# ST_LINK_V2-1.net
KiCad netlist of a schematic drawn in Altium Designer
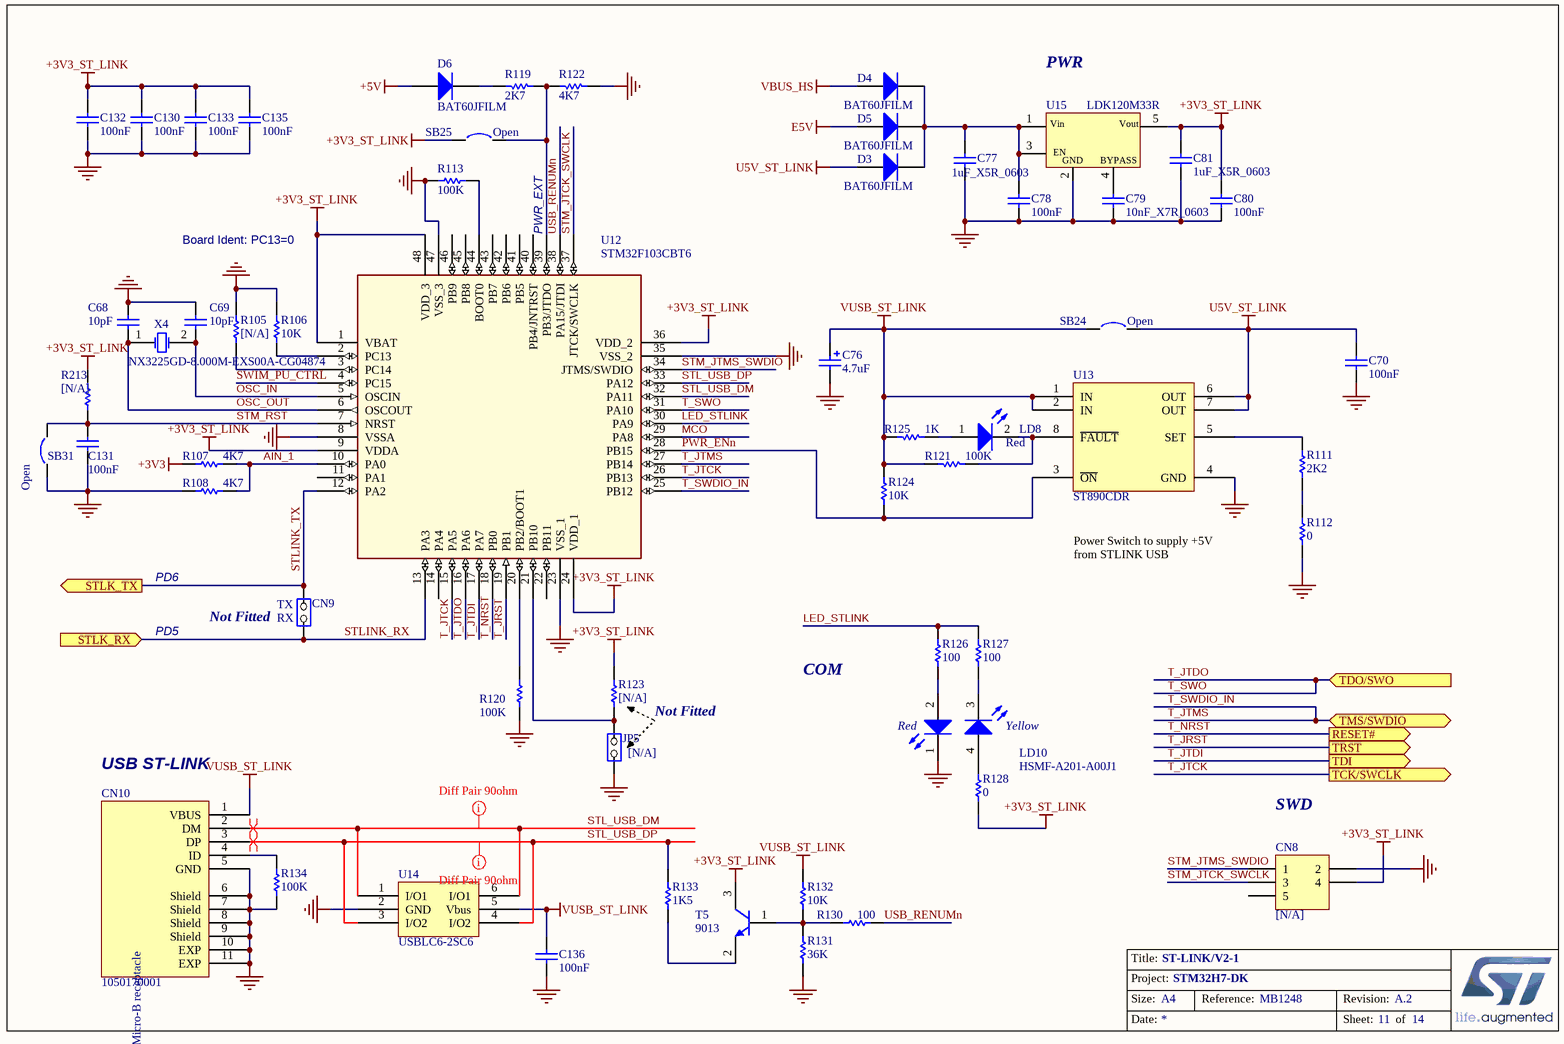
[diagram p0: ST_LINK_V2-1.SCHDOC]

(export (version "E")
  (design (tool "Eeschema 10.0.6"))
  (components
    (comp (ref "C68")
      (value "10pF")
      (footprint "0603C")
      (description "Capacitor 0402 / 0603 / 0805")
      (libsource (lib "MCD_TOOLS") (part "Capacitor_ST"))
    )
    (comp (ref "C69")
      (value "10pF")
      (footprint "0603C")
      (description "Capacitor 0402 / 0603 / 0805")
      (libsource (lib "MCD_TOOLS") (part "Capacitor_ST"))
    )
    (comp (ref "C70")
      (value "100nF")
      (footprint "0603C")
      (description "Capacitor 0402 / 0603 / 0805")
      (libsource (lib "MCD_TOOLS") (part "Capacitor_ST"))
    )
    (comp (ref "C76")
      (value "4.7uF")
      (footprint "TAN-A")
      (description "Polarized Capacitor (Radial)")
      (fields (field (name "PUBLISHER") "Altium Limited"))
      (libsource (lib "*") (part "Cap Pol1"))
    )
    (comp (ref "C77")
      (value "1uF_X5R_0603")
      (footprint "0603C")
      (description "0603  X5R 1µF")
      (fields (field (name "TOLERANCE") "10%"))
      (libsource (lib "MB963_1") (part "CAP SMD 0603  X5R 1µF 25V 10%"))
    )
    (comp (ref "C78")
      (value "100nF")
      (footprint "0603C")
      (description "Capacitor 0402 / 0603 / 0805")
      (libsource (lib "MCD_TOOLS") (part "Capacitor_ST"))
    )
    (comp (ref "C79")
      (value "10nF_X7R_0603")
      (footprint "0603C")
      (description "0603  X7R 10NF")
      (fields (field (name "TOLERANCE") "10%"))
      (libsource (lib "MB963_1") (part "CAP SMD 0603  X7R 10000PF 50V 10%"))
    )
    (comp (ref "C80")
      (value "100nF")
      (footprint "0603C")
      (description "Capacitor 0402 / 0603 / 0805")
      (libsource (lib "MCD_TOOLS") (part "Capacitor_ST"))
    )
    (comp (ref "C81")
      (value "1uF_X5R_0603")
      (footprint "0603C")
      (description "0603  X5R 1µF")
      (fields (field (name "TOLERANCE") "10%"))
      (libsource (lib "MB963_1") (part "CAP SMD 0603  X5R 1µF 25V 10%"))
    )
    (comp (ref "C130")
      (value "100nF")
      (footprint "0603C")
      (description "Capacitor 0402 / 0603 / 0805")
      (libsource (lib "MCD_TOOLS") (part "Capacitor_ST"))
    )
    (comp (ref "C131")
      (value "100nF")
      (footprint "0603C")
      (description "Capacitor 0402 / 0603 / 0805")
      (libsource (lib "MCD_TOOLS") (part "Capacitor_ST"))
    )
    (comp (ref "C132")
      (value "100nF")
      (footprint "0603C")
      (description "Capacitor 0402 / 0603 / 0805")
      (libsource (lib "MCD_TOOLS") (part "Capacitor_ST"))
    )
    (comp (ref "C133")
      (value "100nF")
      (footprint "0603C")
      (description "Capacitor 0402 / 0603 / 0805")
      (libsource (lib "MCD_TOOLS") (part "Capacitor_ST"))
    )
    (comp (ref "C135")
      (value "100nF")
      (footprint "0603C")
      (description "Capacitor 0402 / 0603 / 0805")
      (libsource (lib "MCD_TOOLS") (part "Capacitor_ST"))
    )
    (comp (ref "C136")
      (value "100nF")
      (footprint "0603C")
      (description "Capacitor 0402 / 0603 / 0805")
      (libsource (lib "MCD_TOOLS") (part "Capacitor_ST"))
    )
    (comp (ref "CN8")
      (value "[N/A]")
      (footprint "HDR_2X3-1_2R54-6")
      (description "Header, 3-Pin, Dual row")
      (fields (field (name "PUBLISHER") "Altium Limited"))
      (libsource (lib "Miscellaneous Connectors") (part "Header 3X2"))
    )
    (comp (ref "CN9") (value "[N/A]") (footprint "SIP2") (libsource (lib "MCD_TOOLS") (part "JP2")))
    (comp (ref "CN10")
      (value "1050170001")
      (footprint "MICRO_USB_B_105017")
      (libsource (lib "Smartphone_accessory") (part "1050170001"))
    )
    (comp (ref "D3")
      (value "BAT60JFILM")
      (footprint "SOD-323")
      (libsource (lib "MCD_TOOLS") (part "BAT60JFILM"))
    )
    (comp (ref "D4")
      (value "BAT60JFILM")
      (footprint "SOD-323")
      (libsource (lib "MCD_TOOLS") (part "BAT60JFILM"))
    )
    (comp (ref "D5")
      (value "BAT60JFILM")
      (footprint "SOD-323")
      (libsource (lib "MCD_TOOLS") (part "BAT60JFILM"))
    )
    (comp (ref "D6")
      (value "BAT60JFILM")
      (footprint "SOD-323")
      (description "Default Diode")
      (fields (field (name "PUBLISHER") "Altium Limited"))
      (libsource (lib "MB1144_1") (part "Diode"))
    )
    (comp (ref "JP5") (value "[N/A]") (footprint "SIP2") (libsource (lib "*") (part "JP2")))
    (comp (ref "LD8")
      (value "Red")
      (footprint "0603D")
      (description "Typical RED, GREEN, YELLOW, AMBER GaAs LED")
      (fields (field (name "PUBLISHER") "Altium Limited"))
      (libsource (lib "Miscellaneous Devices") (part "LED2"))
    )
    (comp (ref "LD10")
      (value "HSMF-A201-A00J1")
      (footprint "LED2_3528")
      (libsource (lib "MB819") (part "HSMF-A201-A00J1"))
    )
    (comp (ref "R105")
      (value "[N/A]")
      (footprint "0603R")
      (description "Resistor 0402 or 0603 or 0805")
      (libsource (lib "") (part "Res1_1"))
    )
    (comp (ref "R106")
      (value "10K")
      (footprint "0603R")
      (description "Resistor 0402 or 0603 or 0805")
      (libsource (lib "") (part "Res1_1"))
    )
    (comp (ref "R107")
      (value "4K7")
      (footprint "0603R")
      (description "Resistor 0402 or 0603 or 0805")
      (libsource (lib "") (part "Res1_1"))
    )
    (comp (ref "R108")
      (value "4K7")
      (footprint "0603R")
      (description "Resistor 0402 or 0603 or 0805")
      (libsource (lib "") (part "Res1_1"))
    )
    (comp (ref "R111")
      (value "2K2")
      (footprint "0402R")
      (description "Resistor 0402 or 0603 or 0805")
      (libsource (lib "MCD_TOOLS") (part "Resistor_ST"))
    )
    (comp (ref "R112")
      (value "0")
      (footprint "0603R")
      (description "Resistor")
      (fields (field (name "PUBLISHER") "Altium Limited"))
      (libsource (lib "") (part "Res1_2"))
    )
    (comp (ref "R113")
      (value "100K")
      (footprint "0603R")
      (description "Resistor 0402 or 0603 or 0805")
      (libsource (lib "") (part "Res1_1"))
    )
    (comp (ref "R119")
      (value "2K7")
      (footprint "0603R")
      (description "Resistor")
      (fields (field (name "PUBLISHER") "Altium Limited"))
      (libsource (lib "Miscellaneous Devices") (part "Res1"))
    )
    (comp (ref "R120")
      (value "100K")
      (footprint "0603R")
      (description "Resistor 0402 or 0603 or 0805")
      (libsource (lib "") (part "Res1_1"))
    )
    (comp (ref "R121")
      (value "100K")
      (footprint "0603R")
      (description "Resistor")
      (fields (field (name "PUBLISHER") "Altium Limited"))
      (libsource (lib "*") (part "Res1"))
    )
    (comp (ref "R122")
      (value "4K7")
      (footprint "0603R")
      (description "Resistor")
      (fields (field (name "PUBLISHER") "Altium Limited"))
      (libsource (lib "Miscellaneous Devices") (part "Res1"))
    )
    (comp (ref "R123")
      (value "[N/A]")
      (footprint "0603R")
      (description "Resistor")
      (fields (field (name "PUBLISHER") "Altium Limited"))
      (libsource (lib "") (part "Res1_2"))
    )
    (comp (ref "R124")
      (value "10K")
      (footprint "0402R")
      (description "Resistor 0402 or 0603 or 0805")
      (libsource (lib "MCD_TOOLS") (part "Resistor_ST"))
    )
    (comp (ref "R125")
      (value "1K")
      (footprint "0603R")
      (description "Resistor")
      (fields (field (name "PUBLISHER") "Altium Limited"))
      (libsource (lib "*") (part "Res1"))
    )
    (comp (ref "R126")
      (value "100")
      (footprint "0603R")
      (description "Resistor")
      (fields (field (name "PUBLISHER") "Altium Limited"))
      (libsource (lib "") (part "Res1_2"))
    )
    (comp (ref "R127")
      (value "100")
      (footprint "0603R")
      (description "Resistor")
      (fields (field (name "PUBLISHER") "Altium Limited"))
      (libsource (lib "") (part "Res1_2"))
    )
    (comp (ref "R128")
      (value "0")
      (footprint "0603R")
      (description "Resistor")
      (fields (field (name "PUBLISHER") "Altium Limited"))
      (libsource (lib "") (part "Res1_2"))
    )
    (comp (ref "R130")
      (value "100")
      (footprint "0603R")
      (description "Resistor 0402 or 0603 or 0805")
      (libsource (lib "") (part "Res1_1"))
    )
    (comp (ref "R131")
      (value "36K")
      (footprint "0603R")
      (description "Resistor")
      (fields (field (name "PUBLISHER") "Altium Limited"))
      (libsource (lib "") (part "Res1_2"))
    )
    (comp (ref "R132")
      (value "10K")
      (footprint "0603R")
      (description "Resistor")
      (fields (field (name "PUBLISHER") "Altium Limited"))
      (libsource (lib "") (part "Res1_2"))
    )
    (comp (ref "R133")
      (value "1K5")
      (footprint "0603R")
      (description "Resistor 0402 or 0603 or 0805")
      (libsource (lib "") (part "Res1_1"))
    )
    (comp (ref "R134")
      (value "100K")
      (footprint "0603R")
      (description "Resistor 0402 or 0603 or 0805")
      (libsource (lib "") (part "Res1_1"))
    )
    (comp (ref "R213")
      (value "[N/A]")
      (footprint "0603R")
      (description "Resistor 0402 or 0603 or 0805")
      (libsource (lib "") (part "Res1_1"))
    )
    (comp (ref "SB24")
      (value "Open")
      (footprint "SB_0603")
      (description "Circuit Breaker")
      (fields (field (name "PUBLISHER") "Altium Limited"))
      (libsource (lib "MB1165") (part "Circuit Breaker"))
    )
    (comp (ref "SB25")
      (value "Open")
      (footprint "SB_0603")
      (description "Circuit Breaker")
      (fields (field (name "PUBLISHER") "Altium Limited"))
      (libsource (lib "MB1165") (part "Circuit Breaker"))
    )
    (comp (ref "SB31")
      (value "Open")
      (footprint "SB_0603")
      (description "Circuit Breaker")
      (fields (field (name "PUBLISHER") "Altium Limited"))
      (libsource (lib "MB1165") (part "Circuit Breaker"))
    )
    (comp (ref "T5")
      (value "9013")
      (footprint "SOT-23")
      (description "NPN Bipolar Transistor")
      (fields (field (name "PUBLISHER") "Altium Limited"))
      (libsource (lib "MB1167") (part "NPN"))
    )
    (comp (ref "U12")
      (value "STM32F103CBT6")
      (footprint "LQFP48_0R5_9X9")
      (description "Medium-density performance line ARM-based 32-bit MCU with 64KB Flash")
      (libsource (lib "Nucleo_64") (part "STM32F103CBT6"))
    )
    (comp (ref "U13")
      (value "ST890CDR")
      (footprint "SOIC8_1R27_4R9X6")
      (libsource (lib "MB1167") (part "ST890CDR"))
    )
    (comp (ref "U14")
      (value "USBLC6-2SC6")
      (footprint "SOT23-6L")
      (libsource (lib "MB1137") (part "USBLC6-2SC6"))
    )
    (comp (ref "U15")
      (value "LDK120M33R")
      (footprint "SOT23-5")
      (description "Ultra low drop-low noise BiCMOS voltage, regulators low ESR capacitors compatible")
      (libsource (lib "MB1246") (part "LDK120M33R"))
    )
    (comp (ref "X4")
      (value "NX3225GD-8.000M-EXS00A-CG04874")
      (footprint "XTAL_2SM_3R2X2R5_H1")
      (description "Crystal Oscillator")
      (fields (field (name "PUBLISHER") "Altium Limited"))
      (libsource (lib "MB963_1") (part "XTAL"))
    )
  )
  (nets
    (net (code "1") (name "+3V3") (class "Default")
      (node (ref "R107") (pin "1") (pinfunction "1_1") (pintype "passive"))
    )
    (net (code "2") (name "+3V3_ST_LINK") (class "Default")
      (node (ref "C130") (pin "2") (pinfunction "2_2") (pintype "passive"))
      (node (ref "C132") (pin "2") (pinfunction "2_2") (pintype "passive"))
      (node (ref "C133") (pin "2") (pinfunction "2_2") (pintype "passive"))
      (node (ref "C135") (pin "2") (pinfunction "2_2") (pintype "passive"))
      (node (ref "C80") (pin "2") (pinfunction "2_2") (pintype "passive"))
      (node (ref "C81") (pin "1") (pinfunction "1_1") (pintype "passive"))
      (node (ref "CN8") (pin "4") (pinfunction "4_4") (pintype "passive"))
      (node (ref "R123") (pin "1") (pinfunction "1_1") (pintype "passive"))
      (node (ref "R128") (pin "2") (pinfunction "2_2") (pintype "passive"))
      (node (ref "R213") (pin "2") (pinfunction "2_2") (pintype "passive"))
      (node (ref "SB25") (pin "1") (pinfunction "1_1") (pintype "passive"))
      (node (ref "T5") (pin "3") (pinfunction "C_3") (pintype "passive"))
      (node (ref "U12") (pin "1") (pinfunction "VBAT_1") (pintype "power_in"))
      (node (ref "U12") (pin "24") (pinfunction "VDD_1_24") (pintype "power_in"))
      (node (ref "U12") (pin "36") (pinfunction "VDD_2_36") (pintype "power_in"))
      (node (ref "U12") (pin "48") (pinfunction "VDD_3_48") (pintype "power_in"))
      (node (ref "U12") (pin "9") (pinfunction "VDDA_9") (pintype "power_in"))
      (node (ref "U15") (pin "5") (pinfunction "Vout_5") (pintype "passive"))
    )
    (net (code "3") (name "+5V") (class "Default")
      (node (ref "D6") (pin "1") (pinfunction "A_1") (pintype "passive"))
    )
    (net (code "4") (name "/AIN_1") (class "Default")
      (node (ref "R107") (pin "2") (pinfunction "2_2") (pintype "passive"))
      (node (ref "R108") (pin "2") (pinfunction "2_2") (pintype "passive"))
      (node (ref "U12") (pin "10") (pinfunction "PA0_10") (pintype "bidirectional"))
    )
    (net (code "5") (name "/LED_STLINK") (class "Default")
      (node (ref "R126") (pin "1") (pinfunction "1_1") (pintype "passive"))
      (node (ref "R127") (pin "1") (pinfunction "1_1") (pintype "passive"))
      (node (ref "U12") (pin "30") (pinfunction "PA9_30") (pintype "bidirectional"))
    )
    (net (code "6") (name "/MCO") (class "Default")
      (node (ref "U12") (pin "29") (pinfunction "PA8_29") (pintype "bidirectional"))
    )
    (net (code "7") (name "/OSC_IN") (class "Default")
      (node (ref "C69") (pin "1") (pinfunction "1_1") (pintype "passive"))
      (node (ref "U12") (pin "5") (pinfunction "OSCIN_5") (pintype "input"))
      (node (ref "X4") (pin "2") (pinfunction "OSC2_2") (pintype "passive"))
    )
    (net (code "8") (name "/OSC_OUT") (class "Default")
      (node (ref "C68") (pin "1") (pinfunction "1_1") (pintype "passive"))
      (node (ref "U12") (pin "6") (pinfunction "OSCOUT_6") (pintype "output"))
      (node (ref "X4") (pin "1") (pinfunction "OSC1_1") (pintype "passive"))
    )
    (net (code "9") (name "/PWR_ENn") (class "Default")
      (node (ref "R124") (pin "2") (pinfunction "2_2") (pintype "passive"))
      (node (ref "U12") (pin "28") (pinfunction "PB15_28") (pintype "bidirectional"))
      (node (ref "U13") (pin "3") (pinfunction "~{ON}_3") (pintype "passive"))
    )
    (net (code "10") (name "/STLINK_RX") (class "Default")
      (node (ref "CN9") (pin "1") (pinfunction "COMMON_1") (pintype "passive"))
      (node (ref "U12") (pin "13") (pinfunction "PA3_13") (pintype "bidirectional"))
    )
    (net (code "11") (name "/STLINK_TX") (class "Default")
      (node (ref "CN9") (pin "2") (pinfunction "NO_2") (pintype "passive"))
      (node (ref "U12") (pin "12") (pinfunction "PA2_12") (pintype "bidirectional"))
    )
    (net (code "12") (name "/STL_USB_DM") (class "Default")
      (node (ref "CN10") (pin "2") (pinfunction "DM_2") (pintype "passive"))
      (node (ref "U12") (pin "32") (pinfunction "PA11_32") (pintype "bidirectional"))
      (node (ref "U14") (pin "1") (pinfunction "I/O1_1") (pintype "passive"))
      (node (ref "U14") (pin "6") (pinfunction "I/O1_6") (pintype "passive"))
    )
    (net (code "13") (name "/STL_USB_DP") (class "Default")
      (node (ref "CN10") (pin "3") (pinfunction "DP_3") (pintype "passive"))
      (node (ref "R133") (pin "1") (pinfunction "1_1") (pintype "passive"))
      (node (ref "U12") (pin "33") (pinfunction "PA12_33") (pintype "bidirectional"))
      (node (ref "U14") (pin "3") (pinfunction "I/O2_3") (pintype "passive"))
      (node (ref "U14") (pin "4") (pinfunction "I/O2_4") (pintype "passive"))
    )
    (net (code "14") (name "/STM_JTCK_SWCLK") (class "Default")
      (node (ref "CN8") (pin "3") (pinfunction "3_3") (pintype "passive"))
      (node (ref "U12") (pin "37") (pinfunction "JTCK/SWCLK_37") (pintype "bidirectional"))
    )
    (net (code "15") (name "/STM_JTMS_SWDIO") (class "Default")
      (node (ref "CN8") (pin "1") (pinfunction "1_1") (pintype "passive"))
      (node (ref "U12") (pin "34") (pinfunction "JTMS/SWDIO_34") (pintype "bidirectional"))
    )
    (net (code "16") (name "/STM_RST") (class "Default")
      (node (ref "C131") (pin "2") (pinfunction "2_2") (pintype "passive"))
      (node (ref "R213") (pin "1") (pinfunction "1_1") (pintype "passive"))
      (node (ref "SB31") (pin "2") (pinfunction "2_2") (pintype "passive"))
      (node (ref "U12") (pin "7") (pinfunction "NRST_7") (pintype "input"))
    )
    (net (code "17") (name "/SWIM_PU_CTRL") (class "Default")
      (node (ref "U12") (pin "4") (pinfunction "PC15_4") (pintype "bidirectional"))
    )
    (net (code "18") (name "/T_JRST") (class "Default")
      (node (ref "U12") (pin "19") (pinfunction "PB1_19") (pintype "input"))
    )
    (net (code "19") (name "/T_JTCK") (class "Default")
      (node (ref "U12") (pin "15") (pinfunction "PA5_15") (pintype "bidirectional"))
      (node (ref "U12") (pin "26") (pinfunction "PB13_26") (pintype "bidirectional"))
    )
    (net (code "20") (name "/T_JTDI") (class "Default")
      (node (ref "U12") (pin "17") (pinfunction "PA7_17") (pintype "bidirectional"))
    )
    (net (code "21") (name "/T_JTDO") (class "Default")
      (node (ref "U12") (pin "16") (pinfunction "PA6_16") (pintype "bidirectional"))
      (node (ref "U12") (pin "31") (pinfunction "PA10_31") (pintype "bidirectional"))
    )
    (net (code "22") (name "/T_JTMS") (class "Default")
      (node (ref "U12") (pin "25") (pinfunction "PB12_25") (pintype "bidirectional"))
      (node (ref "U12") (pin "27") (pinfunction "PB14_27") (pintype "bidirectional"))
    )
    (net (code "23") (name "/T_NRST") (class "Default")
      (node (ref "U12") (pin "18") (pinfunction "PB0_18") (pintype "bidirectional"))
    )
    (net (code "24") (name "/USB_RENUMn") (class "Default")
      (node (ref "R130") (pin "2") (pinfunction "2_2") (pintype "passive"))
      (node (ref "U12") (pin "38") (pinfunction "PA15/JTDI_38") (pintype "bidirectional"))
    )
    (net (code "25") (name "E5V") (class "Default")
      (node (ref "D5") (pin "1") (pinfunction "A_1") (pintype "passive"))
    )
    (net (code "26") (name "GND") (class "Default")
      (node (ref "C130") (pin "1") (pinfunction "1_1") (pintype "passive"))
      (node (ref "C131") (pin "1") (pinfunction "1_1") (pintype "passive"))
      (node (ref "C132") (pin "1") (pinfunction "1_1") (pintype "passive"))
      (node (ref "C133") (pin "1") (pinfunction "1_1") (pintype "passive"))
      (node (ref "C135") (pin "1") (pinfunction "1_1") (pintype "passive"))
      (node (ref "C136") (pin "1") (pinfunction "1_1") (pintype "passive"))
      (node (ref "C68") (pin "2") (pinfunction "2_2") (pintype "passive"))
      (node (ref "C69") (pin "2") (pinfunction "2_2") (pintype "passive"))
      (node (ref "C70") (pin "1") (pinfunction "1_1") (pintype "passive"))
      (node (ref "C76") (pin "2") (pinfunction "2_2") (pintype "passive"))
      (node (ref "C77") (pin "1") (pinfunction "1_1") (pintype "passive"))
      (node (ref "C78") (pin "1") (pinfunction "1_1") (pintype "passive"))
      (node (ref "C79") (pin "1") (pinfunction "1_1") (pintype "passive"))
      (node (ref "C80") (pin "1") (pinfunction "1_1") (pintype "passive"))
      (node (ref "C81") (pin "2") (pinfunction "2_2") (pintype "passive"))
      (node (ref "CN10") (pin "10") (pinfunction "EXP_10") (pintype "passive"))
      (node (ref "CN10") (pin "11") (pinfunction "EXP_11") (pintype "passive"))
      (node (ref "CN10") (pin "5") (pinfunction "GND_5") (pintype "passive"))
      (node (ref "CN10") (pin "6") (pinfunction "Shield_6") (pintype "passive"))
      (node (ref "CN10") (pin "7") (pinfunction "Shield_7") (pintype "passive"))
      (node (ref "CN10") (pin "8") (pinfunction "Shield_8") (pintype "passive"))
      (node (ref "CN10") (pin "9") (pinfunction "Shield_9") (pintype "passive"))
      (node (ref "CN8") (pin "2") (pinfunction "2_2") (pintype "passive"))
      (node (ref "JP5") (pin "1") (pinfunction "COMMON_1") (pintype "passive"))
      (node (ref "LD10") (pin "1") (pinfunction "RED_cathode_1") (pintype "passive"))
      (node (ref "R105") (pin "1") (pinfunction "1_1") (pintype "passive"))
      (node (ref "R106") (pin "1") (pinfunction "1_1") (pintype "passive"))
      (node (ref "R108") (pin "1") (pinfunction "1_1") (pintype "passive"))
      (node (ref "R112") (pin "1") (pinfunction "1_1") (pintype "passive"))
      (node (ref "R113") (pin "1") (pinfunction "1_1") (pintype "passive"))
      (node (ref "R120") (pin "1") (pinfunction "1_1") (pintype "passive"))
      (node (ref "R122") (pin "2") (pinfunction "2_2") (pintype "passive"))
      (node (ref "R131") (pin "1") (pinfunction "1_1") (pintype "passive"))
      (node (ref "R134") (pin "2") (pinfunction "2_2") (pintype "passive"))
      (node (ref "SB31") (pin "1") (pinfunction "1_1") (pintype "passive"))
      (node (ref "U12") (pin "23") (pinfunction "VSS_1_23") (pintype "power_in"))
      (node (ref "U12") (pin "35") (pinfunction "VSS_2_35") (pintype "power_in"))
      (node (ref "U12") (pin "47") (pinfunction "VSS_3_47") (pintype "power_in"))
      (node (ref "U12") (pin "8") (pinfunction "VSSA_8") (pintype "power_in"))
      (node (ref "U13") (pin "4") (pinfunction "GND_4") (pintype "passive"))
      (node (ref "U14") (pin "2") (pinfunction "GND_2") (pintype "passive"))
      (node (ref "U15") (pin "2") (pinfunction "GND_2") (pintype "passive"))
    )
    (net (code "27") (name "Net-(CN10-ID)") (class "Default")
      (node (ref "CN10") (pin "4") (pinfunction "ID_4") (pintype "passive"))
      (node (ref "R134") (pin "1") (pinfunction "1_1") (pintype "passive"))
    )
    (net (code "28") (name "Net-(D3-K)") (class "Default")
      (node (ref "C77") (pin "2") (pinfunction "2_2") (pintype "passive"))
      (node (ref "C78") (pin "2") (pinfunction "2_2") (pintype "passive"))
      (node (ref "D3") (pin "2") (pinfunction "K_2") (pintype "passive"))
      (node (ref "D4") (pin "2") (pinfunction "K_2") (pintype "passive"))
      (node (ref "D5") (pin "2") (pinfunction "K_2") (pintype "passive"))
      (node (ref "U15") (pin "1") (pinfunction "Vin_1") (pintype "passive"))
      (node (ref "U15") (pin "3") (pinfunction "CE_3") (pintype "passive"))
    )
    (net (code "29") (name "Net-(D6-K)") (class "Default")
      (node (ref "D6") (pin "2") (pinfunction "K_2") (pintype "passive"))
      (node (ref "R119") (pin "1") (pinfunction "1_1") (pintype "passive"))
    )
    (net (code "30") (name "Net-(JP5-NO)") (class "Default")
      (node (ref "JP5") (pin "2") (pinfunction "NO_2") (pintype "passive"))
      (node (ref "R123") (pin "2") (pinfunction "2_2") (pintype "passive"))
      (node (ref "U12") (pin "21") (pinfunction "PB10_21") (pintype "bidirectional"))
    )
    (net (code "31") (name "Net-(LD8-A)") (class "Default")
      (node (ref "LD8") (pin "1") (pinfunction "A_1") (pintype "passive"))
      (node (ref "R125") (pin "2") (pinfunction "2_2") (pintype "passive"))
    )
    (net (code "32") (name "Net-(LD8-K)") (class "Default")
      (node (ref "LD8") (pin "2") (pinfunction "K_2") (pintype "passive"))
      (node (ref "R121") (pin "2") (pinfunction "2_2") (pintype "passive"))
      (node (ref "U13") (pin "8") (pinfunction "~{FAULT}_8") (pintype "passive"))
    )
    (net (code "33") (name "Net-(LD10-Red_anode)") (class "Default")
      (node (ref "LD10") (pin "2") (pinfunction "Red_anode_2") (pintype "passive"))
      (node (ref "R126") (pin "2") (pinfunction "2_2") (pintype "passive"))
    )
    (net (code "34") (name "Net-(LD10-YellowGreen_anode)") (class "Default")
      (node (ref "LD10") (pin "4") (pinfunction "YellowGreen_anode_4") (pintype "passive"))
      (node (ref "R128") (pin "1") (pinfunction "1_1") (pintype "passive"))
    )
    (net (code "35") (name "Net-(LD10-YellowGreen_cathode)") (class "Default")
      (node (ref "LD10") (pin "3") (pinfunction "YellowGreen_cathode_3") (pintype "passive"))
      (node (ref "R127") (pin "2") (pinfunction "2_2") (pintype "passive"))
    )
    (net (code "36") (name "Net-(R111-Pad1)") (class "Default")
      (node (ref "R111") (pin "1") (pinfunction "1_1") (pintype "passive"))
      (node (ref "R112") (pin "2") (pinfunction "2_2") (pintype "passive"))
    )
    (net (code "37") (name "Net-(T5-B)") (class "Default")
      (node (ref "R130") (pin "1") (pinfunction "1_1") (pintype "passive"))
      (node (ref "R131") (pin "2") (pinfunction "2_2") (pintype "passive"))
      (node (ref "R132") (pin "1") (pinfunction "1_1") (pintype "passive"))
      (node (ref "T5") (pin "1") (pinfunction "B_1") (pintype "passive"))
    )
    (net (code "38") (name "Net-(T5-E)") (class "Default")
      (node (ref "R133") (pin "2") (pinfunction "2_2") (pintype "passive"))
      (node (ref "T5") (pin "2") (pinfunction "E_2") (pintype "passive"))
    )
    (net (code "39") (name "Net-(U12-BOOT0)") (class "Default")
      (node (ref "R113") (pin "2") (pinfunction "2_2") (pintype "passive"))
      (node (ref "U12") (pin "44") (pinfunction "BOOT0_44") (pintype "bidirectional"))
    )
    (net (code "40") (name "Net-(U12-PB2{slash}BOOT1)") (class "Default")
      (node (ref "R120") (pin "2") (pinfunction "2_2") (pintype "passive"))
      (node (ref "U12") (pin "20") (pinfunction "PB2/BOOT1_20") (pintype "bidirectional"))
    )
    (net (code "41") (name "Net-(U12-PB3{slash}JTDO)") (class "Default")
      (node (ref "R119") (pin "2") (pinfunction "2_2") (pintype "passive"))
      (node (ref "R122") (pin "1") (pinfunction "1_1") (pintype "passive"))
      (node (ref "SB25") (pin "2") (pinfunction "2_2") (pintype "passive"))
      (node (ref "U12") (pin "39") (pinfunction "PB3/JTDO_39") (pintype "bidirectional"))
    )
    (net (code "42") (name "Net-(U12-PC13)") (class "Default")
      (node (ref "R106") (pin "2") (pinfunction "2_2") (pintype "passive"))
      (node (ref "U12") (pin "2") (pinfunction "PC13_2") (pintype "bidirectional"))
    )
    (net (code "43") (name "Net-(U12-PC14)") (class "Default")
      (node (ref "R105") (pin "2") (pinfunction "2_2") (pintype "passive"))
      (node (ref "U12") (pin "3") (pinfunction "PC14_3") (pintype "bidirectional"))
    )
    (net (code "44") (name "Net-(U13-SET)") (class "Default")
      (node (ref "R111") (pin "2") (pinfunction "2_2") (pintype "passive"))
      (node (ref "U13") (pin "5") (pinfunction "SET_5") (pintype "passive"))
    )
    (net (code "45") (name "Net-(U15-BYPASS)") (class "Default")
      (node (ref "C79") (pin "2") (pinfunction "2_2") (pintype "passive"))
      (node (ref "U15") (pin "4") (pinfunction "BYPASS_4") (pintype "passive"))
    )
    (net (code "46") (name "U5V_ST_LINK") (class "Default")
      (node (ref "C70") (pin "2") (pinfunction "2_2") (pintype "passive"))
      (node (ref "D3") (pin "1") (pinfunction "A_1") (pintype "passive"))
      (node (ref "SB24") (pin "2") (pinfunction "2_2") (pintype "passive"))
      (node (ref "U13") (pin "6") (pinfunction "OUT_6") (pintype "passive"))
      (node (ref "U13") (pin "7") (pinfunction "OUT_7") (pintype "passive"))
    )
    (net (code "47") (name "VBUS_HS") (class "Default")
      (node (ref "D4") (pin "1") (pinfunction "A_1") (pintype "passive"))
    )
    (net (code "48") (name "VUSB_ST_LINK") (class "Default")
      (node (ref "C136") (pin "2") (pinfunction "2_2") (pintype "passive"))
      (node (ref "C76") (pin "1") (pinfunction "1_1") (pintype "passive"))
      (node (ref "CN10") (pin "1") (pinfunction "VBUS_1") (pintype "passive"))
      (node (ref "R121") (pin "1") (pinfunction "1_1") (pintype "passive"))
      (node (ref "R124") (pin "1") (pinfunction "1_1") (pintype "passive"))
      (node (ref "R125") (pin "1") (pinfunction "1_1") (pintype "passive"))
      (node (ref "R132") (pin "2") (pinfunction "2_2") (pintype "passive"))
      (node (ref "SB24") (pin "1") (pinfunction "1_1") (pintype "passive"))
      (node (ref "U13") (pin "1") (pinfunction "IN_1") (pintype "passive"))
      (node (ref "U13") (pin "2") (pinfunction "IN_2") (pintype "passive"))
      (node (ref "U14") (pin "5") (pinfunction "Vbus_5") (pintype "passive"))
    )
    (net (code "49") (name "unconnected-(CN8-Pad5)") (class "Default")
      (node (ref "CN8") (pin "5") (pinfunction "5_5") (pintype "passive"))
    )
    (net (code "50") (name "unconnected-(U12-PA1-Pad11)") (class "Default")
      (node (ref "U12") (pin "11") (pinfunction "PA1_11") (pintype "bidirectional"))
    )
    (net (code "51") (name "unconnected-(U12-PA4-Pad14)") (class "Default")
      (node (ref "U12") (pin "14") (pinfunction "PA4_14") (pintype "bidirectional"))
    )
    (net (code "52") (name "unconnected-(U12-PB4{slash}JNTRST-Pad40)") (class "Default")
      (node (ref "U12") (pin "40") (pinfunction "PB4/JNTRST_40") (pintype "bidirectional"))
    )
    (net (code "53") (name "unconnected-(U12-PB5-Pad41)") (class "Default")
      (node (ref "U12") (pin "41") (pinfunction "PB5_41") (pintype "bidirectional"))
    )
    (net (code "54") (name "unconnected-(U12-PB6-Pad42)") (class "Default")
      (node (ref "U12") (pin "42") (pinfunction "PB6_42") (pintype "bidirectional"))
    )
    (net (code "55") (name "unconnected-(U12-PB7-Pad43)") (class "Default")
      (node (ref "U12") (pin "43") (pinfunction "PB7_43") (pintype "bidirectional"))
    )
    (net (code "56") (name "unconnected-(U12-PB8-Pad45)") (class "Default")
      (node (ref "U12") (pin "45") (pinfunction "PB8_45") (pintype "bidirectional"))
    )
    (net (code "57") (name "unconnected-(U12-PB9-Pad46)") (class "Default")
      (node (ref "U12") (pin "46") (pinfunction "PB9_46") (pintype "bidirectional"))
    )
    (net (code "58") (name "unconnected-(U12-PB11-Pad22)") (class "Default")
      (node (ref "U12") (pin "22") (pinfunction "PB11_22") (pintype "bidirectional"))
    )
  )
)
